# MultiDrop.net
KiCad netlist of a schematic drawn in EAGLE
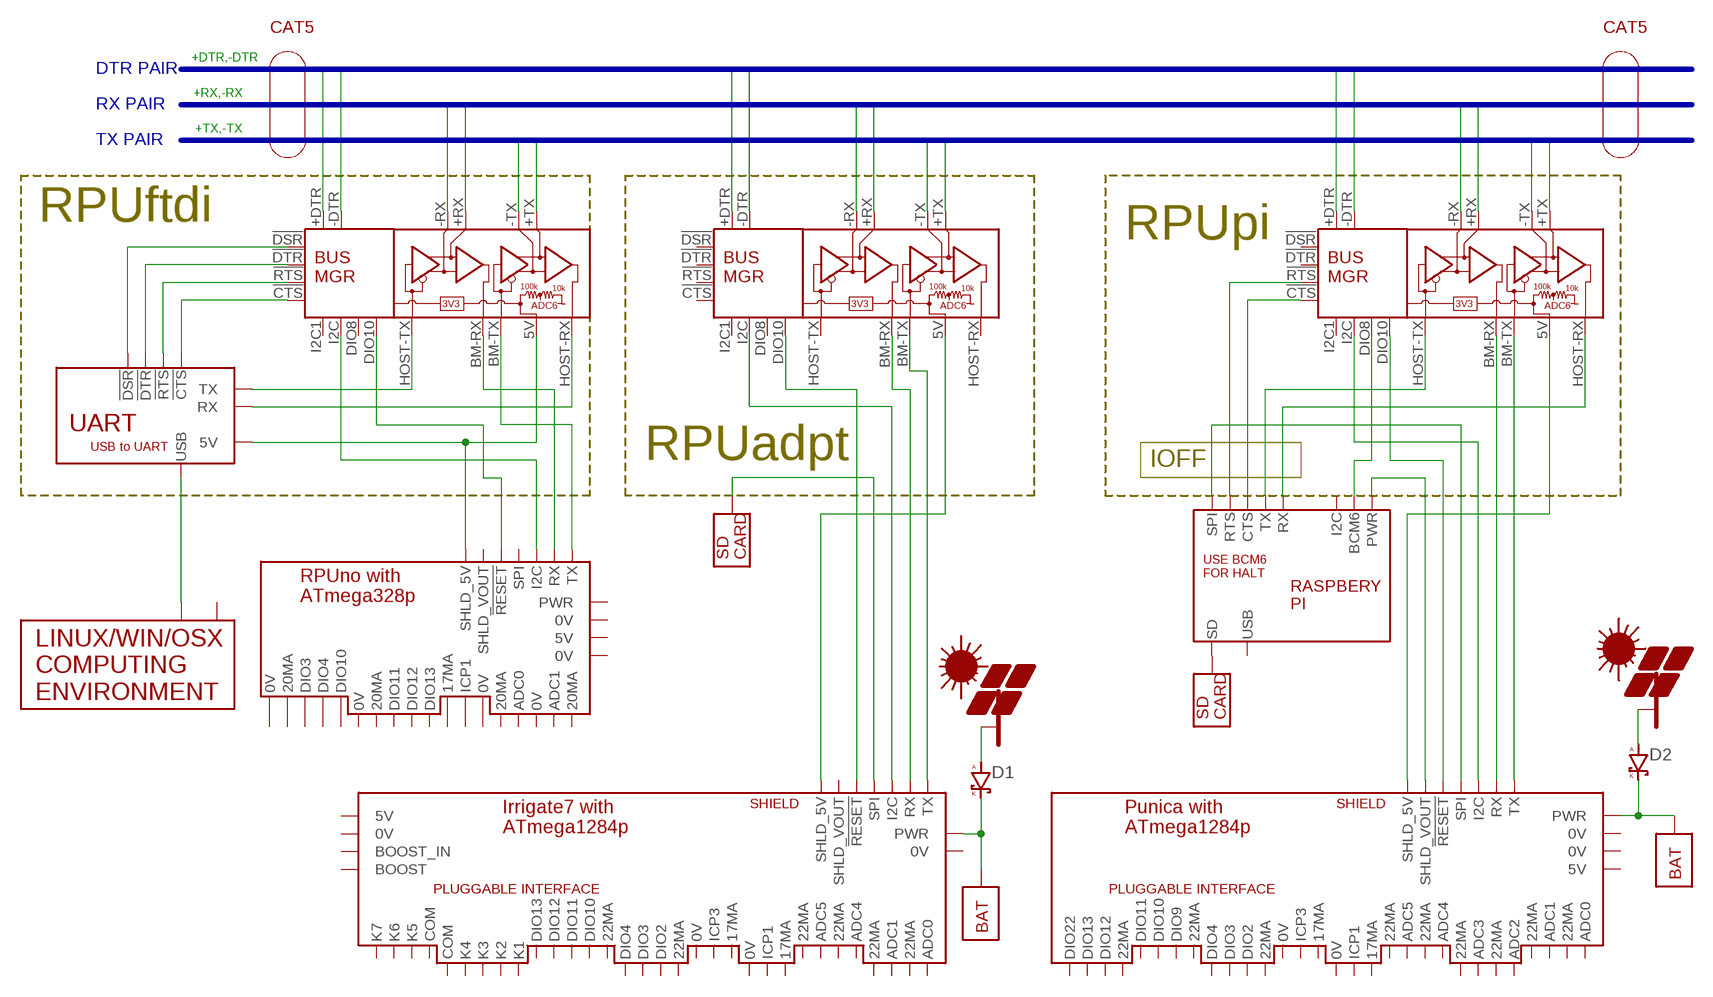
[diagram p0: schematic, sheet 1]

(export (version "E")
  (design (tool "Eeschema 10.0.6"))
  (components
    (comp (ref "BM2")
      (value "RPUNO")
      (footprint "eagle-import:NA-30")
      (libsource (lib "eagle-import") (part "RPUNO"))
    )
    (comp (ref "D1")
      (value "DSMB")
      (footprint "eagle-import:SMB")
      (libsource (lib "eagle-import") (part "DSMB"))
    )
    (comp (ref "D2")
      (value "DSMB")
      (footprint "eagle-import:SMB")
      (libsource (lib "eagle-import") (part "DSMB"))
    )
    (comp (ref "PM1")
      (value "DESKTOP")
      (footprint "eagle-import:NA-30")
      (libsource (lib "eagle-import") (part "DESKTOP"))
    )
    (comp (ref "PV2")
      (value "PV")
      (footprint "eagle-import:NA-30")
      (libsource (lib "eagle-import") (part "PV"))
    )
    (comp (ref "PV4")
      (value "PV")
      (footprint "eagle-import:NA-30")
      (libsource (lib "eagle-import") (part "PV"))
    )
    (comp (ref "SD1")
      (value "SD")
      (footprint "eagle-import:NA-30")
      (libsource (lib "eagle-import") (part "SD"))
    )
    (comp (ref "SD2")
      (value "SD")
      (footprint "eagle-import:NA-30")
      (libsource (lib "eagle-import") (part "SD"))
    )
    (comp (ref "U$1")
      (value "BUS_MGR")
      (footprint "eagle-import:WITH_RPU_NAMES")
      (libsource (lib "eagle-import") (part "BUS_MGR"))
    )
    (comp (ref "U$2")
      (value "BUS_MGR")
      (footprint "eagle-import:WITH_RPU_NAMES")
      (libsource (lib "eagle-import") (part "BUS_MGR"))
    )
    (comp (ref "U$3")
      (value "PI")
      (footprint "eagle-import:NA-30")
      (libsource (lib "eagle-import") (part "PI"))
    )
    (comp (ref "U$4")
      (value "BUS_MGR")
      (footprint "eagle-import:WITH_RPU_NAMES")
      (libsource (lib "eagle-import") (part "BUS_MGR"))
    )
    (comp (ref "U$5")
      (value "IRRIGATE7")
      (footprint "eagle-import:WITH_RPU_NAMES")
      (libsource (lib "eagle-import") (part "IRRIGATE7"))
    )
    (comp (ref "U$7")
      (value "BAT")
      (footprint "eagle-import:NA-30")
      (libsource (lib "eagle-import") (part "BAT"))
    )
    (comp (ref "U$8")
      (value "PUNICA")
      (footprint "eagle-import:WITH_RPU_NAMES")
      (libsource (lib "eagle-import") (part "PUNICA"))
    )
    (comp (ref "U$9")
      (value "BAT")
      (footprint "eagle-import:NA-30")
      (libsource (lib "eagle-import") (part "BAT"))
    )
    (comp (ref "UART1")
      (value "UART")
      (footprint "eagle-import:NA-30")
      (libsource (lib "eagle-import") (part "UART"))
    )
  )
  (nets
    (net (code "10") (name "Net-(BM2-I2C)") (class "Default")
      (node (ref "BM2") (pin "3") (pinfunction "I2C_3") (pintype "bidirectional"))
      (node (ref "U$4") (pin "I2C") (pinfunction "I2C_I2C") (pintype "bidirectional"))
    )
    (net (code "11") (name "Net-(BM2-RX)") (class "Default")
      (node (ref "BM2") (pin "2") (pinfunction "RX_2") (pintype "bidirectional"))
      (node (ref "U$4") (pin "BM-RX") (pinfunction "BM_RX_BM-RX") (pintype "bidirectional"))
    )
    (net (code "12") (name "Net-(BM2-SHLD_5V)") (class "Default")
      (node (ref "BM2") (pin "6") (pinfunction "SHLD_5V_6") (pintype "bidirectional"))
      (node (ref "U$4") (pin "5V") (pinfunction "PWR_5V") (pintype "bidirectional"))
      (node (ref "UART1") (pin "8") (pinfunction "5V_8") (pintype "bidirectional"))
    )
    (net (code "13") (name "Net-(BM2-TX)") (class "Default")
      (node (ref "BM2") (pin "1") (pinfunction "TX_1") (pintype "bidirectional"))
      (node (ref "U$4") (pin "BM-TX") (pinfunction "BM_TX_BM-TX") (pintype "bidirectional"))
    )
    (net (code "14") (name "Net-(BM2-~{RESET})") (class "Default")
      (node (ref "BM2") (pin "5") (pinfunction "~{RESET}_5") (pintype "bidirectional"))
      (node (ref "U$4") (pin "DIO10") (pinfunction "DIO10_DIO10") (pintype "bidirectional"))
    )
    (net (code "15") (name "Net-(PM1-RX)") (class "Default")
      (node (ref "PM1") (pin "1") (pinfunction "RX_1") (pintype "bidirectional"))
      (node (ref "UART1") (pin "7") (pinfunction "USB_7") (pintype "bidirectional"))
    )
    (net (code "16") (name "Net-(PV2-PV_PWR)") (class "Default")
      (node (ref "D1") (pin "A") (pinfunction "A_A") (pintype "passive"))
      (node (ref "PV2") (pin "1") (pinfunction "PV_PWR_1") (pintype "bidirectional"))
    )
    (net (code "17") (name "Net-(PV4-PV_PWR)") (class "Default")
      (node (ref "D2") (pin "A") (pinfunction "A_A") (pintype "passive"))
      (node (ref "PV4") (pin "1") (pinfunction "PV_PWR_1") (pintype "bidirectional"))
    )
    (net (code "18") (name "Net-(SD1-PV_PWR)") (class "Default")
      (node (ref "SD1") (pin "1") (pinfunction "PV_PWR_1") (pintype "bidirectional"))
      (node (ref "U$5") (pin "SPI") (pinfunction "SPI_SPI") (pintype "bidirectional"))
    )
    (net (code "19") (name "Net-(SD2-PV_PWR)") (class "Default")
      (node (ref "SD2") (pin "1") (pinfunction "PV_PWR_1") (pintype "bidirectional"))
      (node (ref "U$3") (pin "9") (pinfunction "SD_9") (pintype "input"))
    )
    (net (code "20") (name "Net-(U$1-BM_RX)") (class "Default")
      (node (ref "U$1") (pin "BM-RX") (pinfunction "BM_RX_BM-RX") (pintype "bidirectional"))
      (node (ref "U$8") (pin "RX") (pinfunction "RX_RX") (pintype "bidirectional"))
    )
    (net (code "21") (name "Net-(U$1-BM_TX)") (class "Default")
      (node (ref "U$1") (pin "BM-TX") (pinfunction "BM_TX_BM-TX") (pintype "bidirectional"))
      (node (ref "U$8") (pin "TX") (pinfunction "TX_TX") (pintype "bidirectional"))
    )
    (net (code "22") (name "Net-(U$1-HOST_RX)") (class "Default")
      (node (ref "U$1") (pin "HOST-RX") (pinfunction "HOST_RX_HOST-RX") (pintype "bidirectional"))
      (node (ref "U$3") (pin "3") (pinfunction "RX_3") (pintype "bidirectional"))
    )
    (net (code "23") (name "Net-(U$1-HOST_TX)") (class "Default")
      (node (ref "U$1") (pin "HOST-TX") (pinfunction "HOST_TX_HOST-TX") (pintype "bidirectional"))
      (node (ref "U$3") (pin "4") (pinfunction "TX_4") (pintype "bidirectional"))
    )
    (net (code "24") (name "Net-(U$1-PWR)") (class "Default")
      (node (ref "U$1") (pin "5V") (pinfunction "PWR_5V") (pintype "bidirectional"))
      (node (ref "U$8") (pin "SHLD_5V") (pinfunction "SHLD_5V_SHLD_5V") (pintype "bidirectional"))
    )
    (net (code "25") (name "Net-(U$1-PadI2C)") (class "Default")
      (node (ref "U$1") (pin "I2C") (pinfunction "I2C_I2C") (pintype "bidirectional"))
      (node (ref "U$8") (pin "I2C") (pinfunction "I2C_I2C") (pintype "bidirectional"))
    )
    (net (code "26") (name "Net-(U$1-~{CTS})") (class "Default")
      (node (ref "U$1") (pin "!CTS") (pinfunction "~{CTS}_!CTS") (pintype "bidirectional"))
      (node (ref "U$3") (pin "1") (pinfunction "CTS_1") (pintype "input"))
    )
    (net (code "27") (name "Net-(U$1-~{RTS})") (class "Default")
      (node (ref "U$1") (pin "!RTS") (pinfunction "~{RTS}_!RTS") (pintype "bidirectional"))
      (node (ref "U$3") (pin "2") (pinfunction "RTS_2") (pintype "input"))
    )
    (net (code "28") (name "Net-(U$2-BM_RX)") (class "Default")
      (node (ref "U$2") (pin "BM-RX") (pinfunction "BM_RX_BM-RX") (pintype "bidirectional"))
      (node (ref "U$5") (pin "RX") (pinfunction "RX_RX") (pintype "bidirectional"))
    )
    (net (code "29") (name "Net-(U$2-BM_TX)") (class "Default")
      (node (ref "U$2") (pin "BM-TX") (pinfunction "BM_TX_BM-TX") (pintype "bidirectional"))
      (node (ref "U$5") (pin "TX") (pinfunction "TX_TX") (pintype "bidirectional"))
    )
    (net (code "30") (name "Net-(U$2-PWR)") (class "Default")
      (node (ref "U$2") (pin "5V") (pinfunction "PWR_5V") (pintype "bidirectional"))
      (node (ref "U$5") (pin "SHLD_5V") (pinfunction "SHLD_5V_SHLD_5V") (pintype "bidirectional"))
    )
    (net (code "31") (name "Net-(U$2-PadI2C)") (class "Default")
      (node (ref "U$2") (pin "I2C") (pinfunction "I2C_I2C") (pintype "bidirectional"))
      (node (ref "U$5") (pin "I2C") (pinfunction "I2C_I2C") (pintype "bidirectional"))
    )
    (net (code "32") (name "Net-(U$3-BCM6)") (class "Default")
      (node (ref "U$1") (pin "DIO8") (pinfunction "DIO8_DIO8") (pintype "bidirectional"))
      (node (ref "U$3") (pin "7") (pinfunction "BCM6_7") (pintype "bidirectional"))
    )
    (net (code "33") (name "Net-(U$3-PWR)") (class "Default")
      (node (ref "U$3") (pin "12") (pinfunction "PWR_12") (pintype "bidirectional"))
      (node (ref "U$8") (pin "SHLD_VOUT") (pinfunction "SHLD_VOUT_SHLD_VOUT") (pintype "bidirectional"))
    )
    (net (code "34") (name "Net-(U$3-SPI)") (class "Default")
      (node (ref "U$3") (pin "10") (pinfunction "SPI_10") (pintype "bidirectional"))
      (node (ref "U$8") (pin "SPI") (pinfunction "SPI_SPI") (pintype "bidirectional"))
    )
    (net (code "35") (name "Net-(U$4-HOST_RX)") (class "Default")
      (node (ref "U$4") (pin "HOST-RX") (pinfunction "HOST_RX_HOST-RX") (pintype "bidirectional"))
      (node (ref "UART1") (pin "5") (pinfunction "RX_5") (pintype "bidirectional"))
    )
    (net (code "36") (name "Net-(U$4-HOST_TX)") (class "Default")
      (node (ref "U$4") (pin "HOST-TX") (pinfunction "HOST_TX_HOST-TX") (pintype "bidirectional"))
      (node (ref "UART1") (pin "6") (pinfunction "TX_6") (pintype "bidirectional"))
    )
    (net (code "37") (name "Net-(U$4-~{CTS})") (class "Default")
      (node (ref "U$4") (pin "!CTS") (pinfunction "~{CTS}_!CTS") (pintype "bidirectional"))
      (node (ref "UART1") (pin "1") (pinfunction "~{CTS}_1") (pintype "input"))
    )
    (net (code "38") (name "Net-(U$4-~{DSR})") (class "Default")
      (node (ref "U$4") (pin "!DSR") (pinfunction "~{DSR}_!DSR") (pintype "bidirectional"))
      (node (ref "UART1") (pin "2") (pinfunction "~{DSR}_2") (pintype "input"))
    )
    (net (code "39") (name "Net-(U$4-~{DTR})") (class "Default")
      (node (ref "U$4") (pin "!DTR") (pinfunction "~{DTR}_!DTR") (pintype "bidirectional"))
      (node (ref "UART1") (pin "3") (pinfunction "~{DTR}_3") (pintype "output"))
    )
    (net (code "40") (name "Net-(U$4-~{RTS})") (class "Default")
      (node (ref "U$4") (pin "!RTS") (pinfunction "~{RTS}_!RTS") (pintype "bidirectional"))
      (node (ref "UART1") (pin "4") (pinfunction "~{RTS}_4") (pintype "output"))
    )
    (net (code "41") (name "Net-(U$5-~{RESET})") (class "Default")
      (node (ref "U$2") (pin "DIO10") (pinfunction "DIO10_DIO10") (pintype "bidirectional"))
      (node (ref "U$5") (pin "!RESET") (pinfunction "~{RESET}_!RESET") (pintype "bidirectional"))
    )
    (net (code "42") (name "Net-(U$7-BAT_PWR)") (class "Default")
      (node (ref "D2") (pin "K") (pinfunction "K_K") (pintype "passive"))
      (node (ref "U$7") (pin "1") (pinfunction "BAT_PWR_1") (pintype "bidirectional"))
      (node (ref "U$8") (pin "PWR") (pinfunction "PWR_PWR") (pintype "bidirectional"))
    )
    (net (code "43") (name "Net-(U$8-~{RESET})") (class "Default")
      (node (ref "U$1") (pin "DIO10") (pinfunction "DIO10_DIO10") (pintype "bidirectional"))
      (node (ref "U$8") (pin "!RESET") (pinfunction "~{RESET}_!RESET") (pintype "bidirectional"))
    )
    (net (code "44") (name "Net-(U$9-BAT_PWR)") (class "Default")
      (node (ref "D1") (pin "K") (pinfunction "K_K") (pintype "passive"))
      (node (ref "U$5") (pin "PWR") (pinfunction "PWR_PWR") (pintype "bidirectional"))
      (node (ref "U$9") (pin "1") (pinfunction "BAT_PWR_1") (pintype "bidirectional"))
    )
    (net (code "45") (name "unconnected-(BM2-0V-Pad9)") (class "Default")
      (node (ref "BM2") (pin "9") (pinfunction "0V_9") (pintype "bidirectional"))
    )
    (net (code "46") (name "unconnected-(BM2-0V-Pad20)") (class "Default")
      (node (ref "BM2") (pin "20") (pinfunction "0V_20") (pintype "bidirectional"))
    )
    (net (code "47") (name "unconnected-(BM2-0V-Pad25)") (class "Default")
      (node (ref "BM2") (pin "25") (pinfunction "0V_25") (pintype "bidirectional"))
    )
    (net (code "48") (name "unconnected-(BM2-0V-Pad26)") (class "Default")
      (node (ref "BM2") (pin "26") (pinfunction "0V_26") (pintype "bidirectional"))
    )
    (net (code "49") (name "unconnected-(BM2-0V-Pad27)") (class "Default")
      (node (ref "BM2") (pin "27") (pinfunction "0V_27") (pintype "bidirectional"))
    )
    (net (code "50") (name "unconnected-(BM2-0V-Pad28)") (class "Default")
      (node (ref "BM2") (pin "28") (pinfunction "0V_28") (pintype "bidirectional"))
    )
    (net (code "51") (name "unconnected-(BM2-5V-Pad19)") (class "Default")
      (node (ref "BM2") (pin "19") (pinfunction "5V_19") (pintype "bidirectional"))
    )
    (net (code "52") (name "unconnected-(BM2-17MA-Pad21)") (class "Default")
      (node (ref "BM2") (pin "21") (pinfunction "17MA_21") (pintype "bidirectional"))
    )
    (net (code "53") (name "unconnected-(BM2-20MA-Pad22)") (class "Default")
      (node (ref "BM2") (pin "22") (pinfunction "20MA_22") (pintype "bidirectional"))
    )
    (net (code "54") (name "unconnected-(BM2-20MA-Pad23)") (class "Default")
      (node (ref "BM2") (pin "23") (pinfunction "20MA_23") (pintype "bidirectional"))
    )
    (net (code "55") (name "unconnected-(BM2-20MA-Pad24)") (class "Default")
      (node (ref "BM2") (pin "24") (pinfunction "20MA_24") (pintype "bidirectional"))
    )
    (net (code "56") (name "unconnected-(BM2-20MA-Pad29)") (class "Default")
      (node (ref "BM2") (pin "29") (pinfunction "20MA_29") (pintype "bidirectional"))
    )
    (net (code "57") (name "unconnected-(BM2-ADC0-Pad10)") (class "Default")
      (node (ref "BM2") (pin "10") (pinfunction "ADC0_10") (pintype "bidirectional"))
    )
    (net (code "58") (name "unconnected-(BM2-ADC1-Pad11)") (class "Default")
      (node (ref "BM2") (pin "11") (pinfunction "ADC1_11") (pintype "bidirectional"))
    )
    (net (code "59") (name "unconnected-(BM2-DIO3-Pad13)") (class "Default")
      (node (ref "BM2") (pin "13") (pinfunction "DIO3_13") (pintype "bidirectional"))
    )
    (net (code "60") (name "unconnected-(BM2-DIO4-Pad14)") (class "Default")
      (node (ref "BM2") (pin "14") (pinfunction "DIO4_14") (pintype "bidirectional"))
    )
    (net (code "61") (name "unconnected-(BM2-DIO10-Pad15)") (class "Default")
      (node (ref "BM2") (pin "15") (pinfunction "DIO10_15") (pintype "bidirectional"))
    )
    (net (code "62") (name "unconnected-(BM2-DIO11-Pad16)") (class "Default")
      (node (ref "BM2") (pin "16") (pinfunction "DIO11_16") (pintype "bidirectional"))
    )
    (net (code "63") (name "unconnected-(BM2-DIO12-Pad17)") (class "Default")
      (node (ref "BM2") (pin "17") (pinfunction "DIO12_17") (pintype "bidirectional"))
    )
    (net (code "64") (name "unconnected-(BM2-DIO13-Pad18)") (class "Default")
      (node (ref "BM2") (pin "18") (pinfunction "DIO13_18") (pintype "bidirectional"))
    )
    (net (code "65") (name "unconnected-(BM2-ICP1-Pad12)") (class "Default")
      (node (ref "BM2") (pin "12") (pinfunction "ICP1_12") (pintype "bidirectional"))
    )
    (net (code "66") (name "unconnected-(BM2-PWR-Pad8)") (class "Default")
      (node (ref "BM2") (pin "8") (pinfunction "PWR_8") (pintype "bidirectional"))
    )
    (net (code "67") (name "unconnected-(BM2-SHLD_VOUT-Pad7)") (class "Default")
      (node (ref "BM2") (pin "7") (pinfunction "SHLD_VOUT_7") (pintype "bidirectional"))
    )
    (net (code "68") (name "unconnected-(BM2-SPI-Pad4)") (class "Default")
      (node (ref "BM2") (pin "4") (pinfunction "SPI_4") (pintype "bidirectional"))
    )
    (net (code "69") (name "unconnected-(PM1-TX-Pad2)") (class "Default")
      (node (ref "PM1") (pin "2") (pinfunction "TX_2") (pintype "bidirectional"))
    )
    (net (code "70") (name "unconnected-(U$1-Pad+DTR)") (class "Default")
      (node (ref "U$1") (pin "+DTR") (pinfunction "+DTR_+DTR") (pintype "bidirectional"))
    )
    (net (code "71") (name "unconnected-(U$1-Pad+RX)") (class "Default")
      (node (ref "U$1") (pin "+RX") (pinfunction "+RX_+RX") (pintype "bidirectional"))
    )
    (net (code "72") (name "unconnected-(U$1-Pad+TX)") (class "Default")
      (node (ref "U$1") (pin "+TX") (pinfunction "+TX_+TX") (pintype "bidirectional"))
    )
    (net (code "73") (name "unconnected-(U$1-Pad-DTR)") (class "Default")
      (node (ref "U$1") (pin "-DTR") (pinfunction "-DTR_-DTR") (pintype "bidirectional"))
    )
    (net (code "74") (name "unconnected-(U$1-Pad-RX)") (class "Default")
      (node (ref "U$1") (pin "-RX") (pinfunction "-RX_-RX") (pintype "bidirectional"))
    )
    (net (code "75") (name "unconnected-(U$1-Pad-TX)") (class "Default")
      (node (ref "U$1") (pin "-TX") (pinfunction "-TX_-TX") (pintype "bidirectional"))
    )
    (net (code "76") (name "unconnected-(U$1-PadI2C1)") (class "Default")
      (node (ref "U$1") (pin "I2C1") (pinfunction "I2C1_I2C1") (pintype "bidirectional"))
    )
    (net (code "77") (name "unconnected-(U$1-~{DSR}-Pad!DSR)") (class "Default")
      (node (ref "U$1") (pin "!DSR") (pinfunction "~{DSR}_!DSR") (pintype "bidirectional"))
    )
    (net (code "78") (name "unconnected-(U$1-~{DTR}-Pad!DTR)") (class "Default")
      (node (ref "U$1") (pin "!DTR") (pinfunction "~{DTR}_!DTR") (pintype "bidirectional"))
    )
    (net (code "79") (name "unconnected-(U$2-HOST_RX-PadHOST-RX)") (class "Default")
      (node (ref "U$2") (pin "HOST-RX") (pinfunction "HOST_RX_HOST-RX") (pintype "bidirectional"))
    )
    (net (code "80") (name "unconnected-(U$2-HOST_TX-PadHOST-TX)") (class "Default")
      (node (ref "U$2") (pin "HOST-TX") (pinfunction "HOST_TX_HOST-TX") (pintype "bidirectional"))
    )
    (net (code "81") (name "unconnected-(U$2-Pad+DTR)") (class "Default")
      (node (ref "U$2") (pin "+DTR") (pinfunction "+DTR_+DTR") (pintype "bidirectional"))
    )
    (net (code "82") (name "unconnected-(U$2-Pad+RX)") (class "Default")
      (node (ref "U$2") (pin "+RX") (pinfunction "+RX_+RX") (pintype "bidirectional"))
    )
    (net (code "83") (name "unconnected-(U$2-Pad+TX)") (class "Default")
      (node (ref "U$2") (pin "+TX") (pinfunction "+TX_+TX") (pintype "bidirectional"))
    )
    (net (code "84") (name "unconnected-(U$2-Pad-DTR)") (class "Default")
      (node (ref "U$2") (pin "-DTR") (pinfunction "-DTR_-DTR") (pintype "bidirectional"))
    )
    (net (code "85") (name "unconnected-(U$2-Pad-RX)") (class "Default")
      (node (ref "U$2") (pin "-RX") (pinfunction "-RX_-RX") (pintype "bidirectional"))
    )
    (net (code "86") (name "unconnected-(U$2-Pad-TX)") (class "Default")
      (node (ref "U$2") (pin "-TX") (pinfunction "-TX_-TX") (pintype "bidirectional"))
    )
    (net (code "87") (name "unconnected-(U$2-PadDIO8)") (class "Default")
      (node (ref "U$2") (pin "DIO8") (pinfunction "DIO8_DIO8") (pintype "bidirectional"))
    )
    (net (code "88") (name "unconnected-(U$2-PadI2C1)") (class "Default")
      (node (ref "U$2") (pin "I2C1") (pinfunction "I2C1_I2C1") (pintype "bidirectional"))
    )
    (net (code "89") (name "unconnected-(U$2-~{CTS}-Pad!CTS)") (class "Default")
      (node (ref "U$2") (pin "!CTS") (pinfunction "~{CTS}_!CTS") (pintype "bidirectional"))
    )
    (net (code "90") (name "unconnected-(U$2-~{DSR}-Pad!DSR)") (class "Default")
      (node (ref "U$2") (pin "!DSR") (pinfunction "~{DSR}_!DSR") (pintype "bidirectional"))
    )
    (net (code "91") (name "unconnected-(U$2-~{DTR}-Pad!DTR)") (class "Default")
      (node (ref "U$2") (pin "!DTR") (pinfunction "~{DTR}_!DTR") (pintype "bidirectional"))
    )
    (net (code "92") (name "unconnected-(U$2-~{RTS}-Pad!RTS)") (class "Default")
      (node (ref "U$2") (pin "!RTS") (pinfunction "~{RTS}_!RTS") (pintype "bidirectional"))
    )
    (net (code "93") (name "unconnected-(U$3-I2C-Pad8)") (class "Default")
      (node (ref "U$3") (pin "8") (pinfunction "I2C_8") (pintype "bidirectional"))
    )
    (net (code "94") (name "unconnected-(U$3-USB-Pad11)") (class "Default")
      (node (ref "U$3") (pin "11") (pinfunction "USB_11") (pintype "input"))
    )
    (net (code "95") (name "unconnected-(U$4-Pad+DTR)") (class "Default")
      (node (ref "U$4") (pin "+DTR") (pinfunction "+DTR_+DTR") (pintype "bidirectional"))
    )
    (net (code "96") (name "unconnected-(U$4-Pad+RX)") (class "Default")
      (node (ref "U$4") (pin "+RX") (pinfunction "+RX_+RX") (pintype "bidirectional"))
    )
    (net (code "97") (name "unconnected-(U$4-Pad+TX)") (class "Default")
      (node (ref "U$4") (pin "+TX") (pinfunction "+TX_+TX") (pintype "bidirectional"))
    )
    (net (code "98") (name "unconnected-(U$4-Pad-DTR)") (class "Default")
      (node (ref "U$4") (pin "-DTR") (pinfunction "-DTR_-DTR") (pintype "bidirectional"))
    )
    (net (code "99") (name "unconnected-(U$4-Pad-RX)") (class "Default")
      (node (ref "U$4") (pin "-RX") (pinfunction "-RX_-RX") (pintype "bidirectional"))
    )
    (net (code "100") (name "unconnected-(U$4-Pad-TX)") (class "Default")
      (node (ref "U$4") (pin "-TX") (pinfunction "-TX_-TX") (pintype "bidirectional"))
    )
    (net (code "101") (name "unconnected-(U$4-PadDIO8)") (class "Default")
      (node (ref "U$4") (pin "DIO8") (pinfunction "DIO8_DIO8") (pintype "bidirectional"))
    )
    (net (code "102") (name "unconnected-(U$4-PadI2C1)") (class "Default")
      (node (ref "U$4") (pin "I2C1") (pinfunction "I2C1_I2C1") (pintype "bidirectional"))
    )
    (net (code "103") (name "unconnected-(U$5-0V-Pad0V@ICP1)") (class "Default")
      (node (ref "U$5") (pin "0V@ICP1") (pinfunction "0V_0V@ICP1") (pintype "bidirectional"))
    )
    (net (code "104") (name "unconnected-(U$5-0V-Pad0V@ICP3)") (class "Default")
      (node (ref "U$5") (pin "0V@ICP3") (pinfunction "0V_0V@ICP3") (pintype "bidirectional"))
    )
    (net (code "105") (name "unconnected-(U$5-0V-Pad0V@PWR)") (class "Default")
      (node (ref "U$5") (pin "0V@PWR") (pinfunction "0V_0V@PWR") (pintype "bidirectional"))
    )
    (net (code "106") (name "unconnected-(U$5-17MA-Pad17MA@ICP1)") (class "Default")
      (node (ref "U$5") (pin "17MA@ICP1") (pinfunction "17MA_17MA@ICP1") (pintype "bidirectional"))
    )
    (net (code "107") (name "unconnected-(U$5-17MA-Pad17MA@ICP3)") (class "Default")
      (node (ref "U$5") (pin "17MA@ICP3") (pinfunction "17MA_17MA@ICP3") (pintype "bidirectional"))
    )
    (net (code "108") (name "unconnected-(U$5-22MA-Pad22MA@ADC0)") (class "Default")
      (node (ref "U$5") (pin "22MA@ADC0") (pinfunction "22MA_22MA@ADC0") (pintype "bidirectional"))
    )
    (net (code "109") (name "unconnected-(U$5-22MA-Pad22MA@ADC1)") (class "Default")
      (node (ref "U$5") (pin "22MA@ADC1") (pinfunction "22MA_22MA@ADC1") (pintype "bidirectional"))
    )
    (net (code "110") (name "unconnected-(U$5-22MA-Pad22MA@ADC4)") (class "Default")
      (node (ref "U$5") (pin "22MA@ADC4") (pinfunction "22MA_22MA@ADC4") (pintype "bidirectional"))
    )
    (net (code "111") (name "unconnected-(U$5-22MA-Pad22MA@ADC5)") (class "Default")
      (node (ref "U$5") (pin "22MA@ADC5") (pinfunction "22MA_22MA@ADC5") (pintype "bidirectional"))
    )
    (net (code "112") (name "unconnected-(U$5-22MA-Pad22MA@DIO2)") (class "Default")
      (node (ref "U$5") (pin "22MA@DIO2") (pinfunction "22MA_22MA@DIO2") (pintype "bidirectional"))
    )
    (net (code "113") (name "unconnected-(U$5-22MA-Pad22MA@DIO10)") (class "Default")
      (node (ref "U$5") (pin "22MA@DIO10") (pinfunction "22MA_22MA@DIO10") (pintype "bidirectional"))
    )
    (net (code "114") (name "unconnected-(U$5-COM-PadCOM@K4)") (class "Default")
      (node (ref "U$5") (pin "COM@K4") (pinfunction "COM_COM@K4") (pintype "bidirectional"))
    )
    (net (code "115") (name "unconnected-(U$5-COM-PadCOM@K5)") (class "Default")
      (node (ref "U$5") (pin "COM@K5") (pinfunction "COM_COM@K5") (pintype "bidirectional"))
    )
    (net (code "116") (name "unconnected-(U$5-Pad0V)") (class "Default")
      (node (ref "U$5") (pin "0V") (pinfunction "0V_0V") (pintype "bidirectional"))
    )
    (net (code "117") (name "unconnected-(U$5-Pad5V)") (class "Default")
      (node (ref "U$5") (pin "5V") (pinfunction "5V_5V") (pintype "bidirectional"))
    )
    (net (code "118") (name "unconnected-(U$5-PadADC0)") (class "Default")
      (node (ref "U$5") (pin "ADC0") (pinfunction "ADC0_ADC0") (pintype "bidirectional"))
    )
    (net (code "119") (name "unconnected-(U$5-PadADC1)") (class "Default")
      (node (ref "U$5") (pin "ADC1") (pinfunction "ADC1_ADC1") (pintype "bidirectional"))
    )
    (net (code "120") (name "unconnected-(U$5-PadADC4)") (class "Default")
      (node (ref "U$5") (pin "ADC4") (pinfunction "ADC4_ADC4") (pintype "bidirectional"))
    )
    (net (code "121") (name "unconnected-(U$5-PadADC5)") (class "Default")
      (node (ref "U$5") (pin "ADC5") (pinfunction "ADC5_ADC5") (pintype "bidirectional"))
    )
    (net (code "122") (name "unconnected-(U$5-PadBOOST)") (class "Default")
      (node (ref "U$5") (pin "BOOST") (pinfunction "BOOST_BOOST") (pintype "bidirectional"))
    )
    (net (code "123") (name "unconnected-(U$5-PadBOOST_IN)") (class "Default")
      (node (ref "U$5") (pin "BOOST_IN") (pinfunction "BOOST_IN_BOOST_IN") (pintype "bidirectional"))
    )
    (net (code "124") (name "unconnected-(U$5-PadDIO2)") (class "Default")
      (node (ref "U$5") (pin "DIO2") (pinfunction "DIO2_DIO2") (pintype "bidirectional"))
    )
    (net (code "125") (name "unconnected-(U$5-PadDIO3)") (class "Default")
      (node (ref "U$5") (pin "DIO3") (pinfunction "DIO3_DIO3") (pintype "bidirectional"))
    )
    (net (code "126") (name "unconnected-(U$5-PadDIO4)") (class "Default")
      (node (ref "U$5") (pin "DIO4") (pinfunction "DIO4_DIO4") (pintype "bidirectional"))
    )
    (net (code "127") (name "unconnected-(U$5-PadDIO10)") (class "Default")
      (node (ref "U$5") (pin "DIO10") (pinfunction "DIO10_DIO10") (pintype "bidirectional"))
    )
    (net (code "128") (name "unconnected-(U$5-PadDIO11)") (class "Default")
      (node (ref "U$5") (pin "DIO11") (pinfunction "DIO11_DIO11") (pintype "bidirectional"))
    )
    (net (code "129") (name "unconnected-(U$5-PadDIO12)") (class "Default")
      (node (ref "U$5") (pin "DIO12") (pinfunction "DIO12_DIO12") (pintype "bidirectional"))
    )
    (net (code "130") (name "unconnected-(U$5-PadDIO13)") (class "Default")
      (node (ref "U$5") (pin "DIO13") (pinfunction "DIO13_DIO13") (pintype "bidirectional"))
    )
    (net (code "131") (name "unconnected-(U$5-PadICP1)") (class "Default")
      (node (ref "U$5") (pin "ICP1") (pinfunction "ICP1_ICP1") (pintype "bidirectional"))
    )
    (net (code "132") (name "unconnected-(U$5-PadICP3)") (class "Default")
      (node (ref "U$5") (pin "ICP3") (pinfunction "ICP3_ICP3") (pintype "bidirectional"))
    )
    (net (code "133") (name "unconnected-(U$5-PadK1)") (class "Default")
      (node (ref "U$5") (pin "K1") (pinfunction "K1_K1") (pintype "bidirectional"))
    )
    (net (code "134") (name "unconnected-(U$5-PadK2)") (class "Default")
      (node (ref "U$5") (pin "K2") (pinfunction "K2_K2") (pintype "bidirectional"))
    )
    (net (code "135") (name "unconnected-(U$5-PadK3)") (class "Default")
      (node (ref "U$5") (pin "K3") (pinfunction "K3_K3") (pintype "bidirectional"))
    )
    (net (code "136") (name "unconnected-(U$5-PadK4)") (class "Default")
      (node (ref "U$5") (pin "K4") (pinfunction "K4_K4") (pintype "bidirectional"))
    )
    (net (code "137") (name "unconnected-(U$5-PadK5)") (class "Default")
      (node (ref "U$5") (pin "K5") (pinfunction "K5_K5") (pintype "bidirectional"))
    )
    (net (code "138") (name "unconnected-(U$5-PadK6)") (class "Default")
      (node (ref "U$5") (pin "K6") (pinfunction "K6_K6") (pintype "bidirectional"))
    )
    (net (code "139") (name "unconnected-(U$5-PadK7)") (class "Default")
      (node (ref "U$5") (pin "K7") (pinfunction "K7_K7") (pintype "bidirectional"))
    )
    (net (code "140") (name "unconnected-(U$5-PadSHLD_VOUT)") (class "Default")
      (node (ref "U$5") (pin "SHLD_VOUT") (pinfunction "SHLD_VOUT_SHLD_VOUT") (pintype "bidirectional"))
    )
    (net (code "141") (name "unconnected-(U$8-0V-Pad0V@ICP1)") (class "Default")
      (node (ref "U$8") (pin "0V@ICP1") (pinfunction "0V_0V@ICP1") (pintype "bidirectional"))
    )
    (net (code "142") (name "unconnected-(U$8-0V-Pad0V@ICP3)") (class "Default")
      (node (ref "U$8") (pin "0V@ICP3") (pinfunction "0V_0V@ICP3") (pintype "bidirectional"))
    )
    (net (code "143") (name "unconnected-(U$8-0V-Pad0V@PWR)") (class "Default")
      (node (ref "U$8") (pin "0V@PWR") (pinfunction "0V_0V@PWR") (pintype "bidirectional"))
    )
    (net (code "144") (name "unconnected-(U$8-17MA-Pad17MA@ICP1)") (class "Default")
      (node (ref "U$8") (pin "17MA@ICP1") (pinfunction "17MA_17MA@ICP1") (pintype "bidirectional"))
    )
    (net (code "145") (name "unconnected-(U$8-17MA-Pad17MA@ICP3)") (class "Default")
      (node (ref "U$8") (pin "17MA@ICP3") (pinfunction "17MA_17MA@ICP3") (pintype "bidirectional"))
    )
    (net (code "146") (name "unconnected-(U$8-22MA-Pad22MA@ADC0)") (class "Default")
      (node (ref "U$8") (pin "22MA@ADC0") (pinfunction "22MA_22MA@ADC0") (pintype "bidirectional"))
    )
    (net (code "147") (name "unconnected-(U$8-22MA-Pad22MA@ADC1)") (class "Default")
      (node (ref "U$8") (pin "22MA@ADC1") (pinfunction "22MA_22MA@ADC1") (pintype "bidirectional"))
    )
    (net (code "148") (name "unconnected-(U$8-22MA-Pad22MA@ADC2)") (class "Default")
      (node (ref "U$8") (pin "22MA@ADC2") (pinfunction "22MA_22MA@ADC2") (pintype "bidirectional"))
    )
    (net (code "149") (name "unconnected-(U$8-22MA-Pad22MA@ADC3)") (class "Default")
      (node (ref "U$8") (pin "22MA@ADC3") (pinfunction "22MA_22MA@ADC3") (pintype "bidirectional"))
    )
    (net (code "150") (name "unconnected-(U$8-22MA-Pad22MA@ADC4)") (class "Default")
      (node (ref "U$8") (pin "22MA@ADC4") (pinfunction "22MA_22MA@ADC4") (pintype "bidirectional"))
    )
    (net (code "151") (name "unconnected-(U$8-22MA-Pad22MA@ADC5)") (class "Default")
      (node (ref "U$8") (pin "22MA@ADC5") (pinfunction "22MA_22MA@ADC5") (pintype "bidirectional"))
    )
    (net (code "152") (name "unconnected-(U$8-22MA-Pad22MA@DIO2)") (class "Default")
      (node (ref "U$8") (pin "22MA@DIO2") (pinfunction "22MA_22MA@DIO2") (pintype "bidirectional"))
    )
    (net (code "153") (name "unconnected-(U$8-22MA-Pad22MA@DIO9)") (class "Default")
      (node (ref "U$8") (pin "22MA@DIO9") (pinfunction "22MA_22MA@DIO9") (pintype "bidirectional"))
    )
    (net (code "154") (name "unconnected-(U$8-22MA-Pad22MA@DIO12)") (class "Default")
      (node (ref "U$8") (pin "22MA@DIO12") (pinfunction "22MA_22MA@DIO12") (pintype "bidirectional"))
    )
    (net (code "155") (name "unconnected-(U$8-Pad0V)") (class "Default")
      (node (ref "U$8") (pin "0V") (pinfunction "0V_0V") (pintype "bidirectional"))
    )
    (net (code "156") (name "unconnected-(U$8-Pad5V)") (class "Default")
      (node (ref "U$8") (pin "5V") (pinfunction "5V_5V") (pintype "bidirectional"))
    )
    (net (code "157") (name "unconnected-(U$8-PadADC0)") (class "Default")
      (node (ref "U$8") (pin "ADC0") (pinfunction "ADC0_ADC0") (pintype "bidirectional"))
    )
    (net (code "158") (name "unconnected-(U$8-PadADC1)") (class "Default")
      (node (ref "U$8") (pin "ADC1") (pinfunction "ADC1_ADC1") (pintype "bidirectional"))
    )
    (net (code "159") (name "unconnected-(U$8-PadADC2)") (class "Default")
      (node (ref "U$8") (pin "ADC2") (pinfunction "ADC2_ADC2") (pintype "bidirectional"))
    )
    (net (code "160") (name "unconnected-(U$8-PadADC3)") (class "Default")
      (node (ref "U$8") (pin "ADC3") (pinfunction "ADC3_ADC3") (pintype "bidirectional"))
    )
    (net (code "161") (name "unconnected-(U$8-PadADC4)") (class "Default")
      (node (ref "U$8") (pin "ADC4") (pinfunction "ADC4_ADC4") (pintype "bidirectional"))
    )
    (net (code "162") (name "unconnected-(U$8-PadADC5)") (class "Default")
      (node (ref "U$8") (pin "ADC5") (pinfunction "ADC5_ADC5") (pintype "bidirectional"))
    )
    (net (code "163") (name "unconnected-(U$8-PadDIO2)") (class "Default")
      (node (ref "U$8") (pin "DIO2") (pinfunction "DIO2_DIO2") (pintype "bidirectional"))
    )
    (net (code "164") (name "unconnected-(U$8-PadDIO3)") (class "Default")
      (node (ref "U$8") (pin "DIO3") (pinfunction "DIO3_DIO3") (pintype "bidirectional"))
    )
    (net (code "165") (name "unconnected-(U$8-PadDIO4)") (class "Default")
      (node (ref "U$8") (pin "DIO4") (pinfunction "DIO4_DIO4") (pintype "bidirectional"))
    )
    (net (code "166") (name "unconnected-(U$8-PadDIO9)") (class "Default")
      (node (ref "U$8") (pin "DIO9") (pinfunction "DIO9_DIO9") (pintype "bidirectional"))
    )
    (net (code "167") (name "unconnected-(U$8-PadDIO10)") (class "Default")
      (node (ref "U$8") (pin "DIO10") (pinfunction "DIO10_DIO10") (pintype "bidirectional"))
    )
    (net (code "168") (name "unconnected-(U$8-PadDIO11)") (class "Default")
      (node (ref "U$8") (pin "DIO11") (pinfunction "DIO11_DIO11") (pintype "bidirectional"))
    )
    (net (code "169") (name "unconnected-(U$8-PadDIO12)") (class "Default")
      (node (ref "U$8") (pin "DIO12") (pinfunction "DIO12_DIO12") (pintype "bidirectional"))
    )
    (net (code "170") (name "unconnected-(U$8-PadDIO13)") (class "Default")
      (node (ref "U$8") (pin "DIO13") (pinfunction "DIO13_DIO13") (pintype "bidirectional"))
    )
    (net (code "171") (name "unconnected-(U$8-PadDIO22)") (class "Default")
      (node (ref "U$8") (pin "DIO22") (pinfunction "DIO22_DIO22") (pintype "bidirectional"))
    )
    (net (code "172") (name "unconnected-(U$8-PadICP1)") (class "Default")
      (node (ref "U$8") (pin "ICP1") (pinfunction "ICP1_ICP1") (pintype "bidirectional"))
    )
    (net (code "173") (name "unconnected-(U$8-PadICP3)") (class "Default")
      (node (ref "U$8") (pin "ICP3") (pinfunction "ICP3_ICP3") (pintype "bidirectional"))
    )
  )
)
